# ESC.net
KiCad netlist of a schematic drawn in Altium Designer
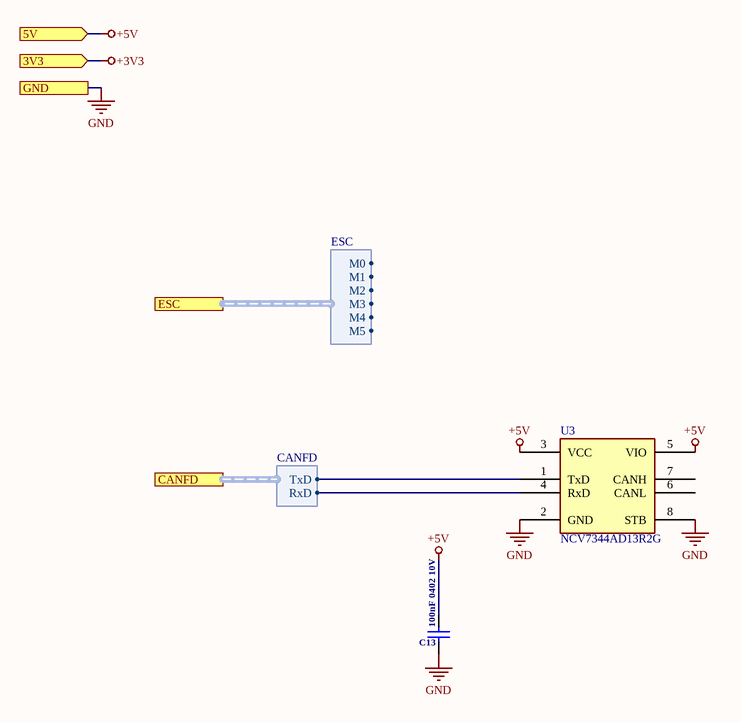
[diagram p0: ESC.SchDoc]

(export (version "E")
  (design (tool "Eeschema 10.0.6"))
  (components
    (comp (ref "C13")
      (value "100nF 0402 10V")
      (description "Cap Ceramic 0.1uF 10V X5R 10% SMD 0402 85C Paper T/R")
      (fields
        (field (name "MANUFACTURER") "Samsung")
        (field (name "MANUFACTURER PART NUMBER") "CL05A104KP5NNNC")
      )
      (libsource (lib "CondensadoresGenericos") (part "CL05A104KP5NNNC 100nF 0402 10V"))
    )
    (comp (ref "U3")
      (value "NCV7344AD13R2G")
      (footprint "SOIC127P600X175-8N")
      (description "IC TRANSCEIVER HALF 1/1 8SOIC")
      (libsource (lib "CAN_Transceivers") (part "NCV7344AD13R2G"))
    )
  )
  (nets
    (net (code "4") (name "+5V") (class "Default")
      (node (ref "C13") (pin "2") (pinfunction "2_2") (pintype "passive"))
      (node (ref "U3") (pin "3") (pinfunction "VCC_3") (pintype "passive"))
      (node (ref "U3") (pin "5") (pinfunction "VIO_5") (pintype "passive"))
    )
    (net (code "5") (name "/RxD") (class "Default")
      (node (ref "U3") (pin "4") (pinfunction "RxD_4") (pintype "passive"))
    )
    (net (code "6") (name "/TxD") (class "Default")
      (node (ref "U3") (pin "1") (pinfunction "TxD_1") (pintype "passive"))
    )
    (net (code "9") (name "GND") (class "Default")
      (node (ref "C13") (pin "1") (pinfunction "1_1") (pintype "passive"))
      (node (ref "U3") (pin "2") (pinfunction "GND_2") (pintype "passive"))
      (node (ref "U3") (pin "8") (pinfunction "STB_8") (pintype "passive"))
    )
    (net (code "10") (name "unconnected-(U3-CANH-Pad7)") (class "Default")
      (node (ref "U3") (pin "7") (pinfunction "CANH_7") (pintype "passive"))
    )
    (net (code "11") (name "unconnected-(U3-CANL-Pad6)") (class "Default")
      (node (ref "U3") (pin "6") (pinfunction "CANL_6") (pintype "passive"))
    )
  )
)
